# Adafruit_DS3502.net
KiCad netlist of a schematic drawn in EAGLE
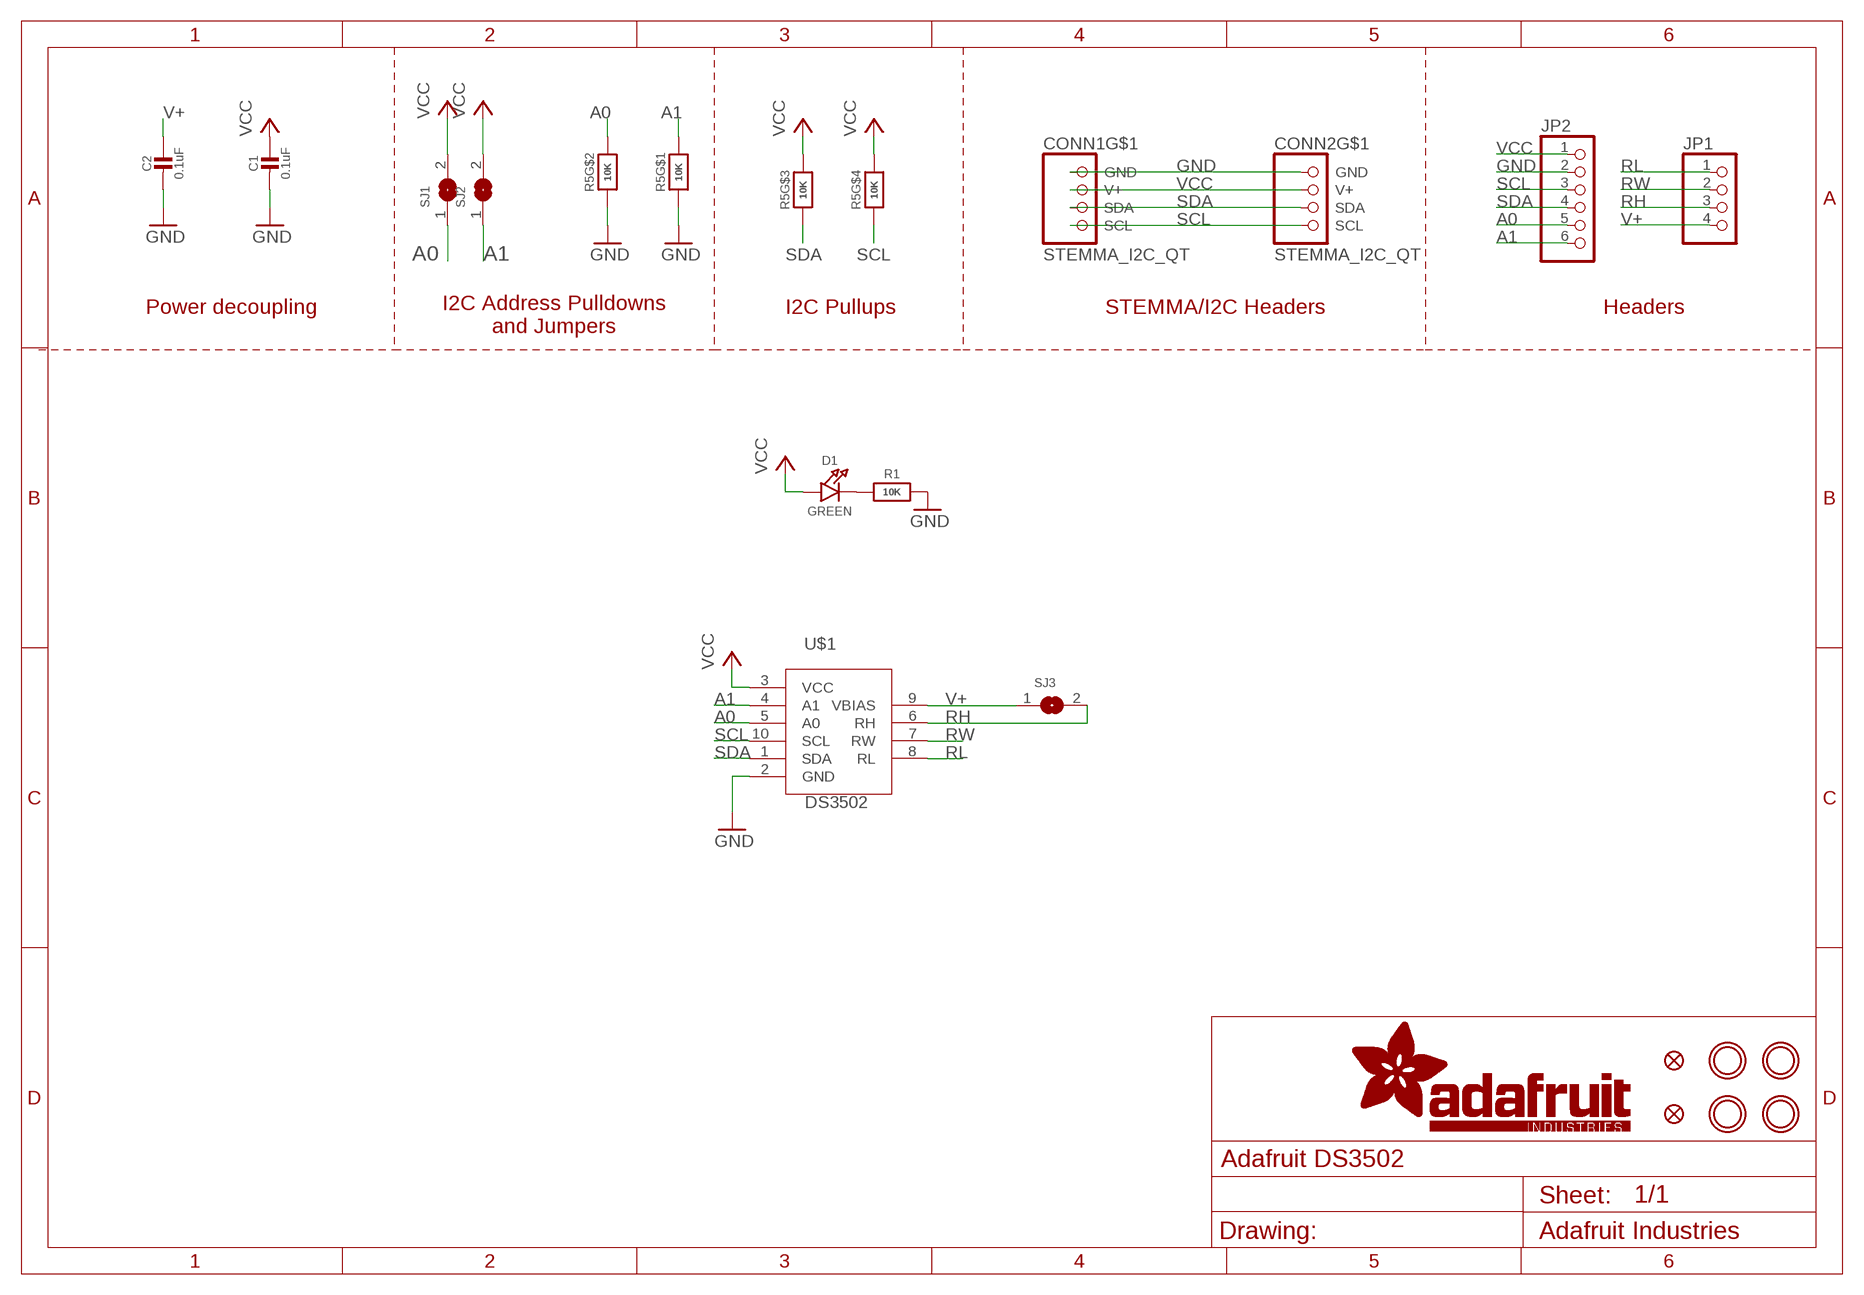
[diagram p0: schematic, sheet 1]

(export (version "E")
  (design (tool "Eeschema 10.0.6"))
  (components
    (comp (ref "C1")
      (value "0.1uF")
      (footprint "eagle-import:0603-NO")
      (libsource (lib "eagle-import") (part "CAP_CERAMIC0603_NO"))
    )
    (comp (ref "C2")
      (value "0.1uF")
      (footprint "eagle-import:0603-NO")
      (libsource (lib "eagle-import") (part "CAP_CERAMIC0603_NO"))
    )
    (comp (ref "CONN1")
      (value "STEMMA_I2C_QT")
      (footprint "eagle-import:JST_SH4")
      (libsource (lib "eagle-import") (part "STEMMA_I2C_QT"))
    )
    (comp (ref "CONN2")
      (value "STEMMA_I2C_QT")
      (footprint "eagle-import:JST_SH4")
      (libsource (lib "eagle-import") (part "STEMMA_I2C_QT"))
    )
    (comp (ref "D1")
      (value "GREEN")
      (footprint "eagle-import:CHIPLED_0603_NOOUTLINE")
      (libsource (lib "eagle-import") (part "LED0603_NOOUTLINE"))
    )
    (comp (ref "FID1")
      (value "FIDUCIAL_1MM")
      (footprint "eagle-import:FIDUCIAL_1MM")
      (libsource (lib "eagle-import") (part "FIDUCIAL_1MM"))
    )
    (comp (ref "FID2")
      (value "FIDUCIAL_1MM")
      (footprint "eagle-import:FIDUCIAL_1MM")
      (libsource (lib "eagle-import") (part "FIDUCIAL_1MM"))
    )
    (comp (ref "JP1")
      (value "HEADER-1X4ROUND")
      (footprint "eagle-import:1X04_ROUND")
      (libsource (lib "eagle-import") (part "HEADER-1X4ROUND"))
    )
    (comp (ref "JP2")
      (value "HEADER-1X6ROUND")
      (footprint "eagle-import:1X06_ROUND")
      (libsource (lib "eagle-import") (part "HEADER-1X6ROUND"))
    )
    (comp (ref "R1")
      (value "10K")
      (footprint "eagle-import:0603-NO")
      (libsource (lib "eagle-import") (part "RESISTOR_0603_NOOUT"))
    )
    (comp (ref "R5")
      (value "10K")
      (footprint "eagle-import:RESPACK_4X0603")
      (libsource (lib "eagle-import") (part "RESISTOR_4PACK"))
    )
    (comp (ref "SJ1")
      (value "SOLDERJUMPER")
      (footprint "eagle-import:SOLDERJUMPER_ARROW_NOPASTE")
      (libsource (lib "eagle-import") (part "SOLDERJUMPER"))
    )
    (comp (ref "SJ2")
      (value "SOLDERJUMPER")
      (footprint "eagle-import:SOLDERJUMPER_ARROW_NOPASTE")
      (libsource (lib "eagle-import") (part "SOLDERJUMPER"))
    )
    (comp (ref "SJ3")
      (value "SOLDERJUMPERCLOSED")
      (footprint "eagle-import:SOLDERJUMPER_CLOSEDWIRE")
      (libsource (lib "eagle-import") (part "SOLDERJUMPERCLOSED"))
    )
    (comp (ref "U$1")
      (value "DS3502")
      (footprint "eagle-import:MSOP10")
      (libsource (lib "eagle-import") (part "DS3502"))
    )
    (comp (ref "U$2")
      (value "MOUNTINGHOLE2.5")
      (footprint "eagle-import:MOUNTINGHOLE_2.5_PLATED")
      (libsource (lib "eagle-import") (part "MOUNTINGHOLE2.5"))
    )
    (comp (ref "U$3")
      (value "MOUNTINGHOLE2.5")
      (footprint "eagle-import:MOUNTINGHOLE_2.5_PLATED")
      (libsource (lib "eagle-import") (part "MOUNTINGHOLE2.5"))
    )
    (comp (ref "U$6")
      (value "MOUNTINGHOLE2.5")
      (footprint "eagle-import:MOUNTINGHOLE_2.5_PLATED")
      (libsource (lib "eagle-import") (part "MOUNTINGHOLE2.5"))
    )
    (comp (ref "U$7")
      (value "MOUNTINGHOLE2.5")
      (footprint "eagle-import:MOUNTINGHOLE_2.5_PLATED")
      (libsource (lib "eagle-import") (part "MOUNTINGHOLE2.5"))
    )
  )
  (nets
    (net (code "1") (name "/A0") (class "Default")
      (node (ref "JP2") (pin "5") (pinfunction "5_5") (pintype "passive"))
      (node (ref "R5") (pin "7") (pinfunction "2_7") (pintype "passive"))
      (node (ref "SJ1") (pin "1") (pinfunction "1_1") (pintype "passive"))
      (node (ref "U$1") (pin "5") (pinfunction "A0_5") (pintype "input"))
    )
    (net (code "2") (name "/A1") (class "Default")
      (node (ref "JP2") (pin "6") (pinfunction "6_6") (pintype "passive"))
      (node (ref "R5") (pin "8") (pinfunction "2_8") (pintype "passive"))
      (node (ref "SJ2") (pin "1") (pinfunction "1_1") (pintype "passive"))
      (node (ref "U$1") (pin "4") (pinfunction "A1_4") (pintype "input"))
    )
    (net (code "3") (name "/RH") (class "Default")
      (node (ref "JP1") (pin "3") (pinfunction "3_3") (pintype "passive"))
      (node (ref "SJ3") (pin "2") (pinfunction "2_2") (pintype "passive"))
      (node (ref "U$1") (pin "6") (pinfunction "RH_6") (pintype "passive"))
    )
    (net (code "4") (name "/RL") (class "Default")
      (node (ref "JP1") (pin "1") (pinfunction "1_1") (pintype "passive"))
      (node (ref "U$1") (pin "8") (pinfunction "RL_8") (pintype "passive"))
    )
    (net (code "5") (name "/RW") (class "Default")
      (node (ref "JP1") (pin "2") (pinfunction "2_2") (pintype "passive"))
      (node (ref "U$1") (pin "7") (pinfunction "RW_7") (pintype "passive"))
    )
    (net (code "6") (name "/SCL") (class "Default")
      (node (ref "CONN1") (pin "4") (pinfunction "SCL_4") (pintype "passive"))
      (node (ref "CONN2") (pin "4") (pinfunction "SCL_4") (pintype "passive"))
      (node (ref "JP2") (pin "3") (pinfunction "3_3") (pintype "passive"))
      (node (ref "R5") (pin "4") (pinfunction "1_4") (pintype "passive"))
      (node (ref "U$1") (pin "10") (pinfunction "SCL_10") (pintype "input"))
    )
    (net (code "7") (name "/SDA") (class "Default")
      (node (ref "CONN1") (pin "3") (pinfunction "SDA_3") (pintype "passive"))
      (node (ref "CONN2") (pin "3") (pinfunction "SDA_3") (pintype "passive"))
      (node (ref "JP2") (pin "4") (pinfunction "4_4") (pintype "passive"))
      (node (ref "R5") (pin "3") (pinfunction "1_3") (pintype "passive"))
      (node (ref "U$1") (pin "1") (pinfunction "SDA_1") (pintype "bidirectional"))
    )
    (net (code "8") (name "/V+") (class "Default")
      (node (ref "C2") (pin "1") (pinfunction "1_1") (pintype "passive"))
      (node (ref "JP1") (pin "4") (pinfunction "4_4") (pintype "passive"))
      (node (ref "SJ3") (pin "1") (pinfunction "1_1") (pintype "passive"))
      (node (ref "U$1") (pin "9") (pinfunction "VBIAS_9") (pintype "power_in"))
    )
    (net (code "9") (name "GND") (class "Default")
      (node (ref "C1") (pin "2") (pinfunction "2_2") (pintype "passive"))
      (node (ref "C2") (pin "2") (pinfunction "2_2") (pintype "passive"))
      (node (ref "CONN1") (pin "1") (pinfunction "GND_1") (pintype "passive"))
      (node (ref "CONN2") (pin "1") (pinfunction "GND_1") (pintype "passive"))
      (node (ref "JP2") (pin "2") (pinfunction "2_2") (pintype "passive"))
      (node (ref "R1") (pin "2") (pinfunction "2_2") (pintype "passive"))
      (node (ref "R5") (pin "1") (pinfunction "1_1") (pintype "passive"))
      (node (ref "R5") (pin "2") (pinfunction "1_2") (pintype "passive"))
      (node (ref "U$1") (pin "2") (pinfunction "GND_2") (pintype "power_in"))
    )
    (net (code "10") (name "Net-(D1-PadC)") (class "Default")
      (node (ref "D1") (pin "C") (pinfunction "C_C") (pintype "passive"))
      (node (ref "R1") (pin "1") (pinfunction "1_1") (pintype "passive"))
    )
    (net (code "11") (name "VCC") (class "Default")
      (node (ref "C1") (pin "1") (pinfunction "1_1") (pintype "passive"))
      (node (ref "CONN1") (pin "2") (pinfunction "V+_2") (pintype "passive"))
      (node (ref "CONN2") (pin "2") (pinfunction "V+_2") (pintype "passive"))
      (node (ref "D1") (pin "A") (pinfunction "A_A") (pintype "passive"))
      (node (ref "JP2") (pin "1") (pinfunction "1_1") (pintype "passive"))
      (node (ref "R5") (pin "5") (pinfunction "2_5") (pintype "passive"))
      (node (ref "R5") (pin "6") (pinfunction "2_6") (pintype "passive"))
      (node (ref "SJ1") (pin "2") (pinfunction "2_2") (pintype "passive"))
      (node (ref "SJ2") (pin "2") (pinfunction "2_2") (pintype "passive"))
      (node (ref "U$1") (pin "3") (pinfunction "VCC_3") (pintype "power_in"))
    )
  )
)
